# Sheet1.net
KiCad netlist of a schematic drawn in Altium Designer
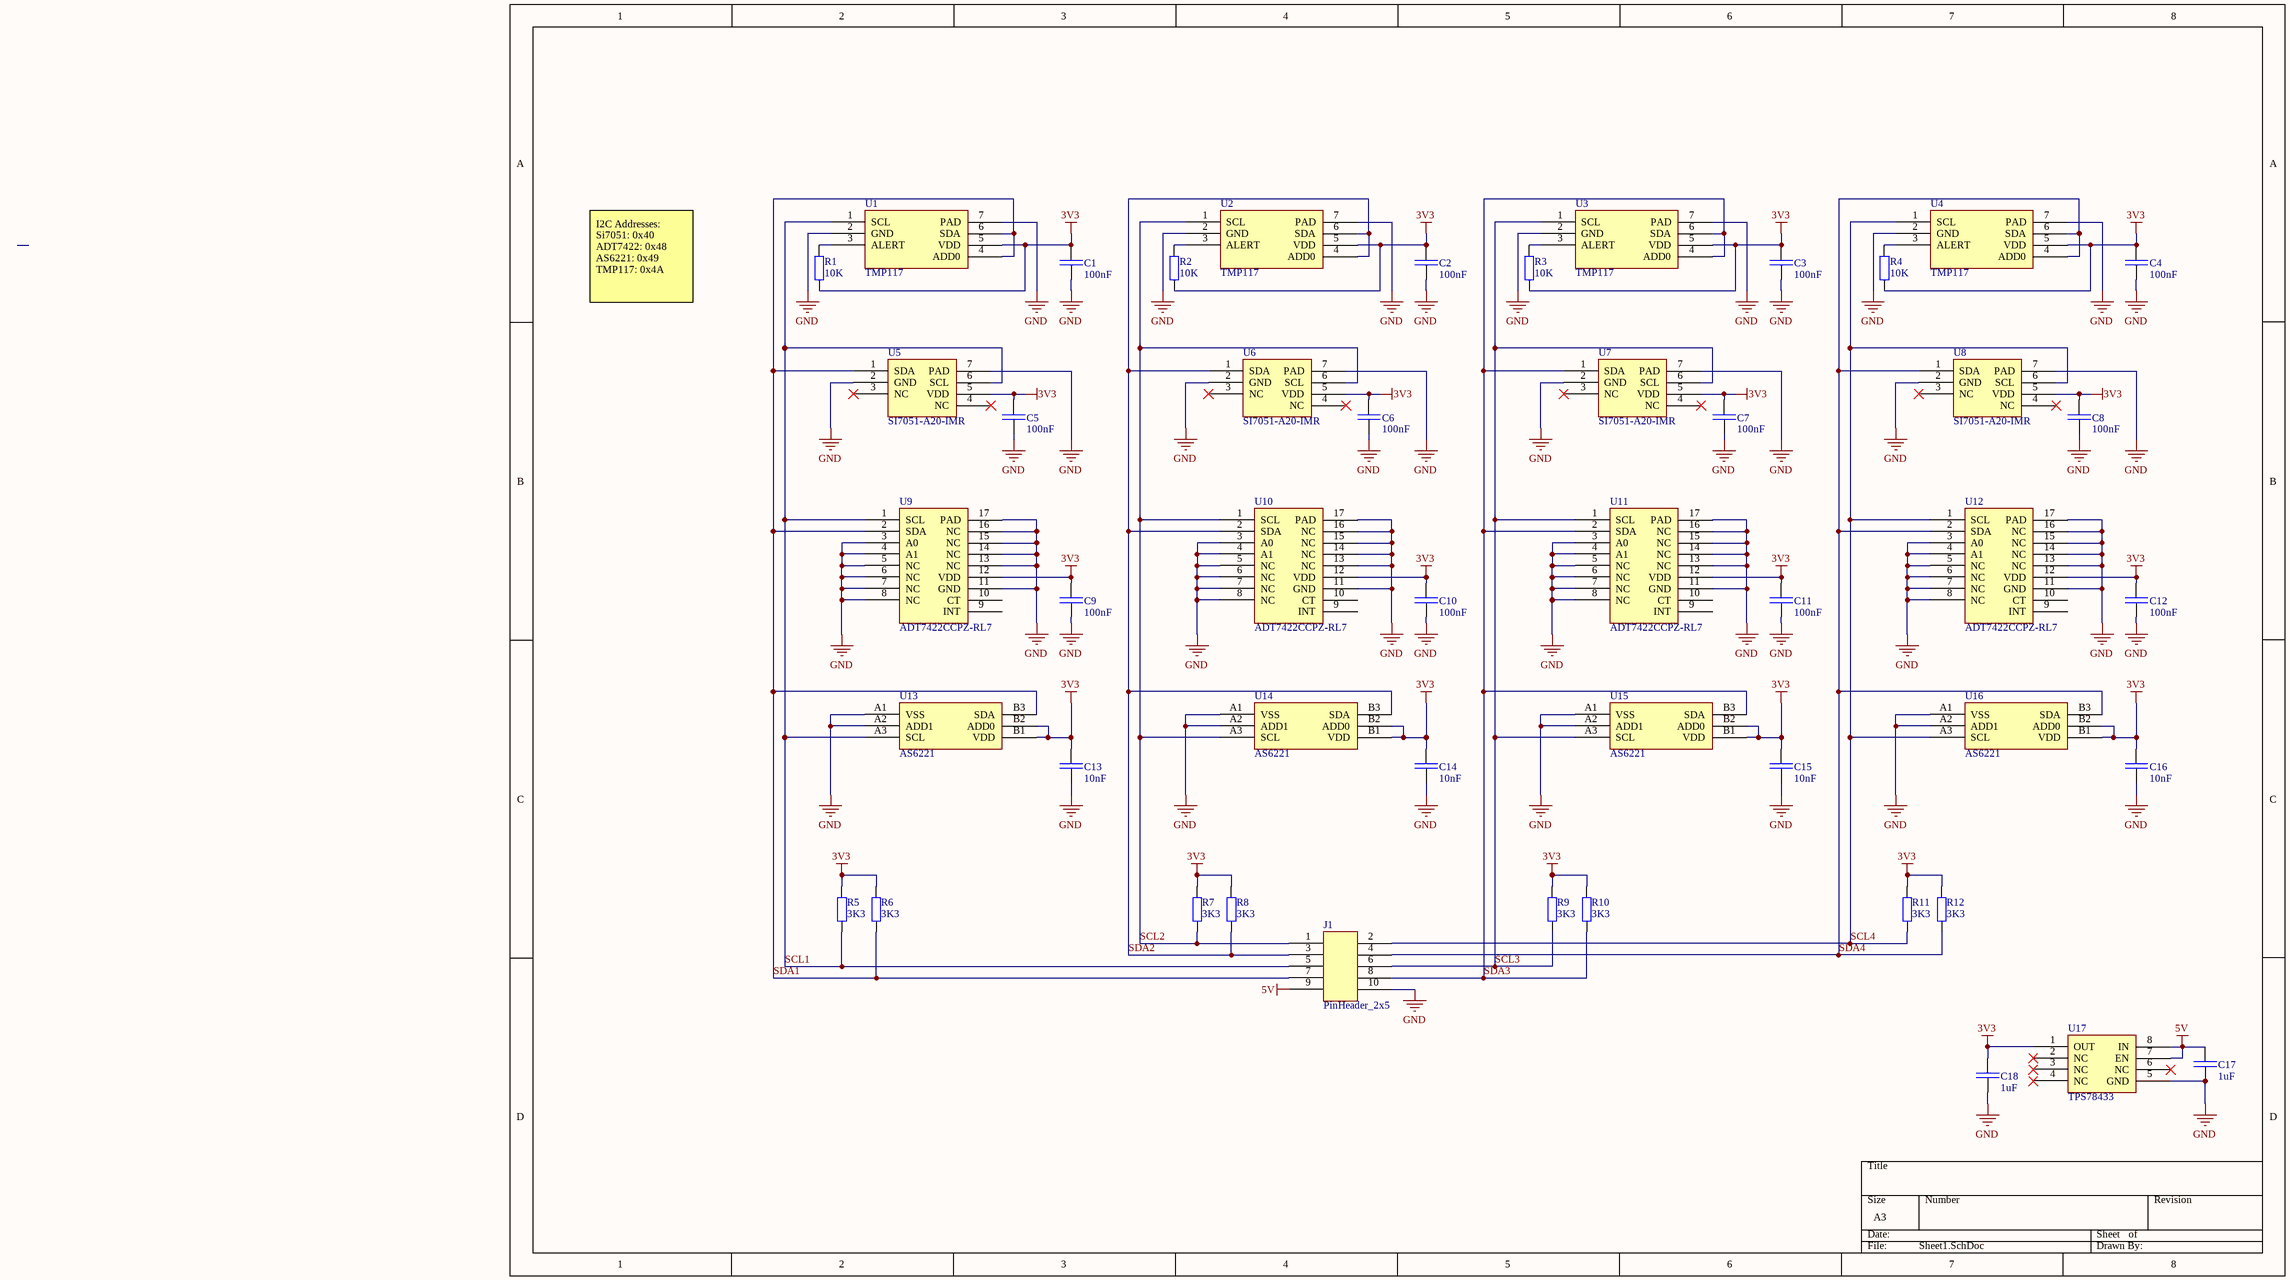
[diagram p0: Sheet1.SchDoc]

(export (version "E")
  (design (tool "Eeschema 10.0.6"))
  (components
    (comp (ref "C1")
      (value "100nF")
      (footprint "CAP_SM0603_YAGEOCC2_N")
      (description "CAP 100nF SM0603 X7R 50V YAGEO CC2")
      (fields
        (field (name "MANUFACTURER") "Yageo")
        (field (name "MANUFACTURER PART NUMBER") "CC0603KRX7R9BB104")
      )
      (libsource (lib "Schlib1") (part "CC0603KRX7R9BB104"))
    )
    (comp (ref "C2")
      (value "100nF")
      (footprint "CAP_SM0603_YAGEOCC2_N")
      (description "CAP 100nF SM0603 X7R 50V YAGEO CC2")
      (fields
        (field (name "MANUFACTURER") "Yageo")
        (field (name "MANUFACTURER PART NUMBER") "CC0603KRX7R9BB104")
      )
      (libsource (lib "Schlib1") (part "CC0603KRX7R9BB104"))
    )
    (comp (ref "C3")
      (value "100nF")
      (footprint "CAP_SM0603_YAGEOCC2_N")
      (description "CAP 100nF SM0603 X7R 50V YAGEO CC2")
      (fields
        (field (name "MANUFACTURER") "Yageo")
        (field (name "MANUFACTURER PART NUMBER") "CC0603KRX7R9BB104")
      )
      (libsource (lib "Schlib1") (part "CC0603KRX7R9BB104"))
    )
    (comp (ref "C4")
      (value "100nF")
      (footprint "CAP_SM0603_YAGEOCC2_N")
      (description "CAP 100nF SM0603 X7R 50V YAGEO CC2")
      (fields
        (field (name "MANUFACTURER") "Yageo")
        (field (name "MANUFACTURER PART NUMBER") "CC0603KRX7R9BB104")
      )
      (libsource (lib "Schlib1") (part "CC0603KRX7R9BB104"))
    )
    (comp (ref "C5")
      (value "100nF")
      (footprint "CAP_SM0603_YAGEOCC2_N")
      (description "CAP 100nF SM0603 X7R 50V YAGEO CC2")
      (fields
        (field (name "MANUFACTURER") "Yageo")
        (field (name "MANUFACTURER PART NUMBER") "CC0603KRX7R9BB104")
      )
      (libsource (lib "Schlib1") (part "CC0603KRX7R9BB104"))
    )
    (comp (ref "C6")
      (value "100nF")
      (footprint "CAP_SM0603_YAGEOCC2_N")
      (description "CAP 100nF SM0603 X7R 50V YAGEO CC2")
      (fields
        (field (name "MANUFACTURER") "Yageo")
        (field (name "MANUFACTURER PART NUMBER") "CC0603KRX7R9BB104")
      )
      (libsource (lib "Schlib1") (part "CC0603KRX7R9BB104"))
    )
    (comp (ref "C7")
      (value "100nF")
      (footprint "CAP_SM0603_YAGEOCC2_N")
      (description "CAP 100nF SM0603 X7R 50V YAGEO CC2")
      (fields
        (field (name "MANUFACTURER") "Yageo")
        (field (name "MANUFACTURER PART NUMBER") "CC0603KRX7R9BB104")
      )
      (libsource (lib "Schlib1") (part "CC0603KRX7R9BB104"))
    )
    (comp (ref "C8")
      (value "100nF")
      (footprint "CAP_SM0603_YAGEOCC2_N")
      (description "CAP 100nF SM0603 X7R 50V YAGEO CC2")
      (fields
        (field (name "MANUFACTURER") "Yageo")
        (field (name "MANUFACTURER PART NUMBER") "CC0603KRX7R9BB104")
      )
      (libsource (lib "Schlib1") (part "CC0603KRX7R9BB104"))
    )
    (comp (ref "C9")
      (value "100nF")
      (footprint "CAP_SM0603_YAGEOCC2_N")
      (description "CAP 100nF SM0603 X7R 50V YAGEO CC2")
      (fields
        (field (name "MANUFACTURER") "Yageo")
        (field (name "MANUFACTURER PART NUMBER") "CC0603KRX7R9BB104")
      )
      (libsource (lib "Schlib1") (part "CC0603KRX7R9BB104"))
    )
    (comp (ref "C10")
      (value "100nF")
      (footprint "CAP_SM0603_YAGEOCC2_N")
      (description "CAP 100nF SM0603 X7R 50V YAGEO CC2")
      (fields
        (field (name "MANUFACTURER") "Yageo")
        (field (name "MANUFACTURER PART NUMBER") "CC0603KRX7R9BB104")
      )
      (libsource (lib "Schlib1") (part "CC0603KRX7R9BB104"))
    )
    (comp (ref "C11")
      (value "100nF")
      (footprint "CAP_SM0603_YAGEOCC2_N")
      (description "CAP 100nF SM0603 X7R 50V YAGEO CC2")
      (fields
        (field (name "MANUFACTURER") "Yageo")
        (field (name "MANUFACTURER PART NUMBER") "CC0603KRX7R9BB104")
      )
      (libsource (lib "Schlib1") (part "CC0603KRX7R9BB104"))
    )
    (comp (ref "C12")
      (value "100nF")
      (footprint "CAP_SM0603_YAGEOCC2_N")
      (description "CAP 100nF SM0603 X7R 50V YAGEO CC2")
      (fields
        (field (name "MANUFACTURER") "Yageo")
        (field (name "MANUFACTURER PART NUMBER") "CC0603KRX7R9BB104")
      )
      (libsource (lib "Schlib1") (part "CC0603KRX7R9BB104"))
    )
    (comp (ref "C13")
      (value "10nF")
      (footprint "CAP_SM0402_YAGEOCC2_N")
      (description "CAP 10nF SM0402 X7R 50V YAGEO CC2")
      (fields
        (field (name "MANUFACTURER") "Yageo")
        (field (name "MANUFACTURER PART NUMBER") "CC0603KRX7R9BB103")
      )
      (libsource (lib "Schlib1") (part "CC0402KRX7R9BB103"))
    )
    (comp (ref "C14")
      (value "10nF")
      (footprint "CAP_SM0402_YAGEOCC2_N")
      (description "CAP 10nF SM0402 X7R 50V YAGEO CC2")
      (fields
        (field (name "MANUFACTURER") "Yageo")
        (field (name "MANUFACTURER PART NUMBER") "CC0603KRX7R9BB103")
      )
      (libsource (lib "Schlib1") (part "CC0402KRX7R9BB103"))
    )
    (comp (ref "C15")
      (value "10nF")
      (footprint "CAP_SM0402_YAGEOCC2_N")
      (description "CAP 10nF SM0402 X7R 50V YAGEO CC2")
      (fields
        (field (name "MANUFACTURER") "Yageo")
        (field (name "MANUFACTURER PART NUMBER") "CC0603KRX7R9BB103")
      )
      (libsource (lib "Schlib1") (part "CC0402KRX7R9BB103"))
    )
    (comp (ref "C16")
      (value "10nF")
      (footprint "CAP_SM0402_YAGEOCC2_N")
      (description "CAP 10nF SM0402 X7R 50V YAGEO CC2")
      (fields
        (field (name "MANUFACTURER") "Yageo")
        (field (name "MANUFACTURER PART NUMBER") "CC0603KRX7R9BB103")
      )
      (libsource (lib "Schlib1") (part "CC0402KRX7R9BB103"))
    )
    (comp (ref "C17")
      (value "1uF")
      (footprint "CAP_SM0805_YAGEOCC2_N")
      (description "CAP 1uF SM0805 X7R 25V YAGEO CC2")
      (fields
        (field (name "MANUFACTURER") "Yageo")
        (field (name "MANUFACTURER PART NUMBER") "CC0805KKX7R8BB105")
      )
      (libsource (lib "symbols") (part "CC0805KKX7R8BB105"))
    )
    (comp (ref "C18")
      (value "1uF")
      (footprint "CAP_SM0805_YAGEOCC2_N")
      (description "CAP 1uF SM0805 X7R 25V YAGEO CC2")
      (fields
        (field (name "MANUFACTURER") "Yageo")
        (field (name "MANUFACTURER PART NUMBER") "CC0805KKX7R8BB105")
      )
      (libsource (lib "symbols") (part "CC0805KKX7R8BB105"))
    )
    (comp (ref "J1")
      (value "PinHeader_2x5")
      (footprint "PinHeader_2x5_2.54mm")
      (description "PinHeader_2x5 2.54mm Pitch")
      (libsource (lib "Schlib1") (part "PinHeader_2x5_2.54mm"))
    )
    (comp (ref "R1")
      (value "10K")
      (footprint "RES_SM0603_YAGEORC_N")
      (description "RES 10K SM0603 YAGEO RC_L")
      (fields
        (field (name "MANUFACTURER") "Yageo")
        (field (name "MANUFACTURER PART NUMBER") "RC0603FR-0710KL")
      )
      (libsource (lib "Schlib1") (part "RC0603FR-0710KL"))
    )
    (comp (ref "R2")
      (value "10K")
      (footprint "RES_SM0603_YAGEORC_N")
      (description "RES 10K SM0603 YAGEO RC_L")
      (fields
        (field (name "MANUFACTURER") "Yageo")
        (field (name "MANUFACTURER PART NUMBER") "RC0603FR-0710KL")
      )
      (libsource (lib "Schlib1") (part "RC0603FR-0710KL"))
    )
    (comp (ref "R3")
      (value "10K")
      (footprint "RES_SM0603_YAGEORC_N")
      (description "RES 10K SM0603 YAGEO RC_L")
      (fields
        (field (name "MANUFACTURER") "Yageo")
        (field (name "MANUFACTURER PART NUMBER") "RC0603FR-0710KL")
      )
      (libsource (lib "Schlib1") (part "RC0603FR-0710KL"))
    )
    (comp (ref "R4")
      (value "10K")
      (footprint "RES_SM0603_YAGEORC_N")
      (description "RES 10K SM0603 YAGEO RC_L")
      (fields
        (field (name "MANUFACTURER") "Yageo")
        (field (name "MANUFACTURER PART NUMBER") "RC0603FR-0710KL")
      )
      (libsource (lib "Schlib1") (part "RC0603FR-0710KL"))
    )
    (comp (ref "R5")
      (value "3K3")
      (footprint "RES_SM0603_YAGEORC_N")
      (description "RES 3.3K SM0603 YAGEO RC_L")
      (fields
        (field (name "MANUFACTURER") "Yageo")
        (field (name "MANUFACTURER PART NUMBER") "RC0603FR-0710KL")
      )
      (libsource (lib "Schlib1") (part "RC0603FR-073K3L"))
    )
    (comp (ref "R6")
      (value "3K3")
      (footprint "RES_SM0603_YAGEORC_N")
      (description "RES 3.3K SM0603 YAGEO RC_L")
      (fields
        (field (name "MANUFACTURER") "Yageo")
        (field (name "MANUFACTURER PART NUMBER") "RC0603FR-0710KL")
      )
      (libsource (lib "Schlib1") (part "RC0603FR-073K3L"))
    )
    (comp (ref "R7")
      (value "3K3")
      (footprint "RES_SM0603_YAGEORC_N")
      (description "RES 3.3K SM0603 YAGEO RC_L")
      (fields
        (field (name "MANUFACTURER") "Yageo")
        (field (name "MANUFACTURER PART NUMBER") "RC0603FR-0710KL")
      )
      (libsource (lib "Schlib1") (part "RC0603FR-073K3L"))
    )
    (comp (ref "R8")
      (value "3K3")
      (footprint "RES_SM0603_YAGEORC_N")
      (description "RES 3.3K SM0603 YAGEO RC_L")
      (fields
        (field (name "MANUFACTURER") "Yageo")
        (field (name "MANUFACTURER PART NUMBER") "RC0603FR-0710KL")
      )
      (libsource (lib "Schlib1") (part "RC0603FR-073K3L"))
    )
    (comp (ref "R9")
      (value "3K3")
      (footprint "RES_SM0603_YAGEORC_N")
      (description "RES 3.3K SM0603 YAGEO RC_L")
      (fields
        (field (name "MANUFACTURER") "Yageo")
        (field (name "MANUFACTURER PART NUMBER") "RC0603FR-0710KL")
      )
      (libsource (lib "Schlib1") (part "RC0603FR-073K3L"))
    )
    (comp (ref "R10")
      (value "3K3")
      (footprint "RES_SM0603_YAGEORC_N")
      (description "RES 3.3K SM0603 YAGEO RC_L")
      (fields
        (field (name "MANUFACTURER") "Yageo")
        (field (name "MANUFACTURER PART NUMBER") "RC0603FR-0710KL")
      )
      (libsource (lib "Schlib1") (part "RC0603FR-073K3L"))
    )
    (comp (ref "R11")
      (value "3K3")
      (footprint "RES_SM0603_YAGEORC_N")
      (description "RES 3.3K SM0603 YAGEO RC_L")
      (fields
        (field (name "MANUFACTURER") "Yageo")
        (field (name "MANUFACTURER PART NUMBER") "RC0603FR-0710KL")
      )
      (libsource (lib "Schlib1") (part "RC0603FR-073K3L"))
    )
    (comp (ref "R12")
      (value "3K3")
      (footprint "RES_SM0603_YAGEORC_N")
      (description "RES 3.3K SM0603 YAGEO RC_L")
      (fields
        (field (name "MANUFACTURER") "Yageo")
        (field (name "MANUFACTURER PART NUMBER") "RC0603FR-0710KL")
      )
      (libsource (lib "Schlib1") (part "RC0603FR-073K3L"))
    )
    (comp (ref "U1")
      (value "TMP117")
      (footprint "TMP117(N/M)AIDRV_WSON")
      (description "TMP117 High-Accuracy, Low-Power, Digital Temperature Sensor, -55°C bis 150°C, 16b 6-WSON (2x2)")
      (libsource (lib "Schlib1") (part "TMP117NAIDRVR"))
    )
    (comp (ref "U2")
      (value "TMP117")
      (footprint "TMP117(N/M)AIDRV_WSON")
      (description "TMP117 High-Accuracy, Low-Power, Digital Temperature Sensor, -55°C bis 150°C, 16b 6-WSON (2x2)")
      (libsource (lib "Schlib1") (part "TMP117NAIDRVR"))
    )
    (comp (ref "U3")
      (value "TMP117")
      (footprint "TMP117(N/M)AIDRV_WSON")
      (description "TMP117 High-Accuracy, Low-Power, Digital Temperature Sensor, -55°C bis 150°C, 16b 6-WSON (2x2)")
      (libsource (lib "Schlib1") (part "TMP117NAIDRVR"))
    )
    (comp (ref "U4")
      (value "TMP117")
      (footprint "TMP117(N/M)AIDRV_WSON")
      (description "TMP117 High-Accuracy, Low-Power, Digital Temperature Sensor, -55°C bis 150°C, 16b 6-WSON (2x2)")
      (libsource (lib "Schlib1") (part "TMP117NAIDRVR"))
    )
    (comp (ref "U5")
      (value "SI7051-A20-IMR")
      (footprint "SI7050/1/2/3/4/5")
      (description "Si7051-A20 Temperature Sensor ±0.1°C maximum accuracy, Digital I2C, -40°C ~ 125°C 14b 6-DFN (3x3)")
      (libsource (lib "Schlib1") (part "SI7051-A20-IMR"))
    )
    (comp (ref "U6")
      (value "SI7051-A20-IMR")
      (footprint "SI7050/1/2/3/4/5")
      (description "Si7051-A20 Temperature Sensor ±0.1°C maximum accuracy, Digital I2C, -40°C ~ 125°C 14b 6-DFN (3x3)")
      (libsource (lib "Schlib1") (part "SI7051-A20-IMR"))
    )
    (comp (ref "U7")
      (value "SI7051-A20-IMR")
      (footprint "SI7050/1/2/3/4/5")
      (description "Si7051-A20 Temperature Sensor ±0.1°C maximum accuracy, Digital I2C, -40°C ~ 125°C 14b 6-DFN (3x3)")
      (libsource (lib "Schlib1") (part "SI7051-A20-IMR"))
    )
    (comp (ref "U8")
      (value "SI7051-A20-IMR")
      (footprint "SI7050/1/2/3/4/5")
      (description "Si7051-A20 Temperature Sensor ±0.1°C maximum accuracy, Digital I2C, -40°C ~ 125°C 14b 6-DFN (3x3)")
      (libsource (lib "Schlib1") (part "SI7051-A20-IMR"))
    )
    (comp (ref "U9")
      (value "ADT7422CCPZ-RL7")
      (footprint "ADT7422_QFN")
      (libsource (lib "Schlib1") (part "ADT7422CCPZ-RL7"))
    )
    (comp (ref "U10")
      (value "ADT7422CCPZ-RL7")
      (footprint "ADT7422_QFN")
      (libsource (lib "Schlib1") (part "ADT7422CCPZ-RL7"))
    )
    (comp (ref "U11")
      (value "ADT7422CCPZ-RL7")
      (footprint "ADT7422_QFN")
      (libsource (lib "Schlib1") (part "ADT7422CCPZ-RL7"))
    )
    (comp (ref "U12")
      (value "ADT7422CCPZ-RL7")
      (footprint "ADT7422_QFN")
      (libsource (lib "Schlib1") (part "ADT7422CCPZ-RL7"))
    )
    (comp (ref "U13")
      (value "AS6221")
      (footprint "AS6221_BGA")
      (description "AS6221 Temperature Sensor Digital -40°C ~ 125°C 16b 6-WLCSP (1.5x1.03)")
      (libsource (lib "Schlib1") (part "AS6221-AWLT-S"))
    )
    (comp (ref "U14")
      (value "AS6221")
      (footprint "AS6221_BGA")
      (description "AS6221 Temperature Sensor Digital -40°C ~ 125°C 16b 6-WLCSP (1.5x1.03)")
      (libsource (lib "Schlib1") (part "AS6221-AWLT-S"))
    )
    (comp (ref "U15")
      (value "AS6221")
      (footprint "AS6221_BGA")
      (description "AS6221 Temperature Sensor Digital -40°C ~ 125°C 16b 6-WLCSP (1.5x1.03)")
      (libsource (lib "Schlib1") (part "AS6221-AWLT-S"))
    )
    (comp (ref "U16")
      (value "AS6221")
      (footprint "AS6221_BGA")
      (description "AS6221 Temperature Sensor Digital -40°C ~ 125°C 16b 6-WLCSP (1.5x1.03)")
      (libsource (lib "Schlib1") (part "AS6221-AWLT-S"))
    )
    (comp (ref "U17")
      (value "TPS78433")
      (footprint "TPS784xxxQDRBRQ1_SON")
      (libsource (lib "symbols") (part "TPS78433QWDRBRQ1"))
    )
  )
  (nets
    (net (code "1") (name "/SCL1") (class "Default")
      (node (ref "J1") (pin "5") (pintype "passive"))
      (node (ref "R5") (pin "1") (pintype "passive"))
      (node (ref "U1") (pin "1") (pinfunction "SCL_1") (pintype "passive"))
      (node (ref "U13") (pin "A3") (pinfunction "SCL_A3") (pintype "passive"))
      (node (ref "U5") (pin "6") (pinfunction "SCL_6") (pintype "passive"))
      (node (ref "U9") (pin "1") (pinfunction "SCL_1") (pintype "passive"))
    )
    (net (code "2") (name "/SCL2") (class "Default")
      (node (ref "J1") (pin "1") (pintype "passive"))
      (node (ref "R7") (pin "1") (pintype "passive"))
      (node (ref "U10") (pin "1") (pinfunction "SCL_1") (pintype "passive"))
      (node (ref "U14") (pin "A3") (pinfunction "SCL_A3") (pintype "passive"))
      (node (ref "U2") (pin "1") (pinfunction "SCL_1") (pintype "passive"))
      (node (ref "U6") (pin "6") (pinfunction "SCL_6") (pintype "passive"))
    )
    (net (code "3") (name "/SCL3") (class "Default")
      (node (ref "J1") (pin "6") (pintype "passive"))
      (node (ref "R9") (pin "1") (pintype "passive"))
      (node (ref "U11") (pin "1") (pinfunction "SCL_1") (pintype "passive"))
      (node (ref "U15") (pin "A3") (pinfunction "SCL_A3") (pintype "passive"))
      (node (ref "U3") (pin "1") (pinfunction "SCL_1") (pintype "passive"))
      (node (ref "U7") (pin "6") (pinfunction "SCL_6") (pintype "passive"))
    )
    (net (code "4") (name "/SCL4") (class "Default")
      (node (ref "J1") (pin "2") (pintype "passive"))
      (node (ref "R11") (pin "1") (pintype "passive"))
      (node (ref "U12") (pin "1") (pinfunction "SCL_1") (pintype "passive"))
      (node (ref "U16") (pin "A3") (pinfunction "SCL_A3") (pintype "passive"))
      (node (ref "U4") (pin "1") (pinfunction "SCL_1") (pintype "passive"))
      (node (ref "U8") (pin "6") (pinfunction "SCL_6") (pintype "passive"))
    )
    (net (code "5") (name "/SDA1") (class "Default")
      (node (ref "J1") (pin "7") (pintype "passive"))
      (node (ref "R6") (pin "1") (pintype "passive"))
      (node (ref "U1") (pin "4") (pinfunction "ADD0_4") (pintype "passive"))
      (node (ref "U1") (pin "6") (pinfunction "SDA_6") (pintype "passive"))
      (node (ref "U13") (pin "B3") (pinfunction "SDA_B3") (pintype "passive"))
      (node (ref "U5") (pin "1") (pinfunction "SDA_1") (pintype "passive"))
      (node (ref "U9") (pin "2") (pinfunction "SDA_2") (pintype "passive"))
    )
    (net (code "6") (name "/SDA2") (class "Default")
      (node (ref "J1") (pin "3") (pintype "passive"))
      (node (ref "R8") (pin "1") (pintype "passive"))
      (node (ref "U10") (pin "2") (pinfunction "SDA_2") (pintype "passive"))
      (node (ref "U14") (pin "B3") (pinfunction "SDA_B3") (pintype "passive"))
      (node (ref "U2") (pin "4") (pinfunction "ADD0_4") (pintype "passive"))
      (node (ref "U2") (pin "6") (pinfunction "SDA_6") (pintype "passive"))
      (node (ref "U6") (pin "1") (pinfunction "SDA_1") (pintype "passive"))
    )
    (net (code "7") (name "/SDA3") (class "Default")
      (node (ref "J1") (pin "8") (pintype "passive"))
      (node (ref "R10") (pin "1") (pintype "passive"))
      (node (ref "U11") (pin "2") (pinfunction "SDA_2") (pintype "passive"))
      (node (ref "U15") (pin "B3") (pinfunction "SDA_B3") (pintype "passive"))
      (node (ref "U3") (pin "4") (pinfunction "ADD0_4") (pintype "passive"))
      (node (ref "U3") (pin "6") (pinfunction "SDA_6") (pintype "passive"))
      (node (ref "U7") (pin "1") (pinfunction "SDA_1") (pintype "passive"))
    )
    (net (code "8") (name "/SDA4") (class "Default")
      (node (ref "J1") (pin "4") (pintype "passive"))
      (node (ref "R12") (pin "1") (pintype "passive"))
      (node (ref "U12") (pin "2") (pinfunction "SDA_2") (pintype "passive"))
      (node (ref "U16") (pin "B3") (pinfunction "SDA_B3") (pintype "passive"))
      (node (ref "U4") (pin "4") (pinfunction "ADD0_4") (pintype "passive"))
      (node (ref "U4") (pin "6") (pinfunction "SDA_6") (pintype "passive"))
      (node (ref "U8") (pin "1") (pinfunction "SDA_1") (pintype "passive"))
    )
    (net (code "9") (name "3V3") (class "Default")
      (node (ref "C1") (pin "2") (pintype "passive"))
      (node (ref "C10") (pin "2") (pintype "passive"))
      (node (ref "C11") (pin "2") (pintype "passive"))
      (node (ref "C12") (pin "2") (pintype "passive"))
      (node (ref "C13") (pin "1") (pintype "passive"))
      (node (ref "C14") (pin "1") (pintype "passive"))
      (node (ref "C15") (pin "1") (pintype "passive"))
      (node (ref "C16") (pin "1") (pintype "passive"))
      (node (ref "C18") (pin "2") (pintype "passive"))
      (node (ref "C2") (pin "2") (pintype "passive"))
      (node (ref "C3") (pin "2") (pintype "passive"))
      (node (ref "C4") (pin "2") (pintype "passive"))
      (node (ref "C5") (pin "2") (pintype "passive"))
      (node (ref "C6") (pin "2") (pintype "passive"))
      (node (ref "C7") (pin "2") (pintype "passive"))
      (node (ref "C8") (pin "2") (pintype "passive"))
      (node (ref "C9") (pin "2") (pintype "passive"))
      (node (ref "R1") (pin "1") (pintype "passive"))
      (node (ref "R10") (pin "2") (pintype "passive"))
      (node (ref "R11") (pin "2") (pintype "passive"))
      (node (ref "R12") (pin "2") (pintype "passive"))
      (node (ref "R2") (pin "1") (pintype "passive"))
      (node (ref "R3") (pin "1") (pintype "passive"))
      (node (ref "R4") (pin "1") (pintype "passive"))
      (node (ref "R5") (pin "2") (pintype "passive"))
      (node (ref "R6") (pin "2") (pintype "passive"))
      (node (ref "R7") (pin "2") (pintype "passive"))
      (node (ref "R8") (pin "2") (pintype "passive"))
      (node (ref "R9") (pin "2") (pintype "passive"))
      (node (ref "U1") (pin "5") (pinfunction "VDD_5") (pintype "passive"))
      (node (ref "U10") (pin "12") (pinfunction "VDD_12") (pintype "passive"))
      (node (ref "U11") (pin "12") (pinfunction "VDD_12") (pintype "passive"))
      (node (ref "U12") (pin "12") (pinfunction "VDD_12") (pintype "passive"))
      (node (ref "U13") (pin "B1") (pinfunction "VDD_B1") (pintype "passive"))
      (node (ref "U13") (pin "B2") (pinfunction "ADD0_B2") (pintype "passive"))
      (node (ref "U14") (pin "B1") (pinfunction "VDD_B1") (pintype "passive"))
      (node (ref "U14") (pin "B2") (pinfunction "ADD0_B2") (pintype "passive"))
      (node (ref "U15") (pin "B1") (pinfunction "VDD_B1") (pintype "passive"))
      (node (ref "U15") (pin "B2") (pinfunction "ADD0_B2") (pintype "passive"))
      (node (ref "U16") (pin "B1") (pinfunction "VDD_B1") (pintype "passive"))
      (node (ref "U16") (pin "B2") (pinfunction "ADD0_B2") (pintype "passive"))
      (node (ref "U17") (pin "1") (pinfunction "OUT_1") (pintype "passive"))
      (node (ref "U2") (pin "5") (pinfunction "VDD_5") (pintype "passive"))
      (node (ref "U3") (pin "5") (pinfunction "VDD_5") (pintype "passive"))
      (node (ref "U4") (pin "5") (pinfunction "VDD_5") (pintype "passive"))
      (node (ref "U5") (pin "5") (pinfunction "VDD_5") (pintype "passive"))
      (node (ref "U6") (pin "5") (pinfunction "VDD_5") (pintype "passive"))
      (node (ref "U7") (pin "5") (pinfunction "VDD_5") (pintype "passive"))
      (node (ref "U8") (pin "5") (pinfunction "VDD_5") (pintype "passive"))
      (node (ref "U9") (pin "12") (pinfunction "VDD_12") (pintype "passive"))
    )
    (net (code "10") (name "5V") (class "Default")
      (node (ref "C17") (pin "2") (pintype "passive"))
      (node (ref "J1") (pin "9") (pintype "passive"))
      (node (ref "U17") (pin "7") (pinfunction "EN_7") (pintype "passive"))
      (node (ref "U17") (pin "8") (pinfunction "IN_8") (pintype "passive"))
    )
    (net (code "11") (name "GND") (class "Default")
      (node (ref "C1") (pin "1") (pintype "passive"))
      (node (ref "C10") (pin "1") (pintype "passive"))
      (node (ref "C11") (pin "1") (pintype "passive"))
      (node (ref "C12") (pin "1") (pintype "passive"))
      (node (ref "C13") (pin "2") (pintype "passive"))
      (node (ref "C14") (pin "2") (pintype "passive"))
      (node (ref "C15") (pin "2") (pintype "passive"))
      (node (ref "C16") (pin "2") (pintype "passive"))
      (node (ref "C17") (pin "1") (pintype "passive"))
      (node (ref "C18") (pin "1") (pintype "passive"))
      (node (ref "C2") (pin "1") (pintype "passive"))
      (node (ref "C3") (pin "1") (pintype "passive"))
      (node (ref "C4") (pin "1") (pintype "passive"))
      (node (ref "C5") (pin "1") (pintype "passive"))
      (node (ref "C6") (pin "1") (pintype "passive"))
      (node (ref "C7") (pin "1") (pintype "passive"))
      (node (ref "C8") (pin "1") (pintype "passive"))
      (node (ref "C9") (pin "1") (pintype "passive"))
      (node (ref "J1") (pin "10") (pintype "passive"))
      (node (ref "U1") (pin "2") (pinfunction "GND_2") (pintype "passive"))
      (node (ref "U1") (pin "7") (pinfunction "PAD_7") (pintype "passive"))
      (node (ref "U10") (pin "11") (pinfunction "GND_11") (pintype "passive"))
      (node (ref "U10") (pin "13") (pinfunction "NC_13") (pintype "passive"))
      (node (ref "U10") (pin "14") (pinfunction "NC_14") (pintype "passive"))
      (node (ref "U10") (pin "15") (pinfunction "NC_15") (pintype "passive"))
      (node (ref "U10") (pin "16") (pinfunction "NC_16") (pintype "passive"))
      (node (ref "U10") (pin "17") (pinfunction "PAD_17") (pintype "passive"))
      (node (ref "U10") (pin "3") (pinfunction "A0_3") (pintype "passive"))
      (node (ref "U10") (pin "4") (pinfunction "A1_4") (pintype "passive"))
      (node (ref "U10") (pin "5") (pinfunction "NC_5") (pintype "passive"))
      (node (ref "U10") (pin "6") (pinfunction "NC_6") (pintype "passive"))
      (node (ref "U10") (pin "7") (pinfunction "NC_7") (pintype "passive"))
      (node (ref "U10") (pin "8") (pinfunction "NC_8") (pintype "passive"))
      (node (ref "U11") (pin "11") (pinfunction "GND_11") (pintype "passive"))
      (node (ref "U11") (pin "13") (pinfunction "NC_13") (pintype "passive"))
      (node (ref "U11") (pin "14") (pinfunction "NC_14") (pintype "passive"))
      (node (ref "U11") (pin "15") (pinfunction "NC_15") (pintype "passive"))
      (node (ref "U11") (pin "16") (pinfunction "NC_16") (pintype "passive"))
      (node (ref "U11") (pin "17") (pinfunction "PAD_17") (pintype "passive"))
      (node (ref "U11") (pin "3") (pinfunction "A0_3") (pintype "passive"))
      (node (ref "U11") (pin "4") (pinfunction "A1_4") (pintype "passive"))
      (node (ref "U11") (pin "5") (pinfunction "NC_5") (pintype "passive"))
      (node (ref "U11") (pin "6") (pinfunction "NC_6") (pintype "passive"))
      (node (ref "U11") (pin "7") (pinfunction "NC_7") (pintype "passive"))
      (node (ref "U11") (pin "8") (pinfunction "NC_8") (pintype "passive"))
      (node (ref "U12") (pin "11") (pinfunction "GND_11") (pintype "passive"))
      (node (ref "U12") (pin "13") (pinfunction "NC_13") (pintype "passive"))
      (node (ref "U12") (pin "14") (pinfunction "NC_14") (pintype "passive"))
      (node (ref "U12") (pin "15") (pinfunction "NC_15") (pintype "passive"))
      (node (ref "U12") (pin "16") (pinfunction "NC_16") (pintype "passive"))
      (node (ref "U12") (pin "17") (pinfunction "PAD_17") (pintype "passive"))
      (node (ref "U12") (pin "3") (pinfunction "A0_3") (pintype "passive"))
      (node (ref "U12") (pin "4") (pinfunction "A1_4") (pintype "passive"))
      (node (ref "U12") (pin "5") (pinfunction "NC_5") (pintype "passive"))
      (node (ref "U12") (pin "6") (pinfunction "NC_6") (pintype "passive"))
      (node (ref "U12") (pin "7") (pinfunction "NC_7") (pintype "passive"))
      (node (ref "U12") (pin "8") (pinfunction "NC_8") (pintype "passive"))
      (node (ref "U13") (pin "A1") (pinfunction "VSS_A1") (pintype "passive"))
      (node (ref "U13") (pin "A2") (pinfunction "ADD1_A2") (pintype "passive"))
      (node (ref "U14") (pin "A1") (pinfunction "VSS_A1") (pintype "passive"))
      (node (ref "U14") (pin "A2") (pinfunction "ADD1_A2") (pintype "passive"))
      (node (ref "U15") (pin "A1") (pinfunction "VSS_A1") (pintype "passive"))
      (node (ref "U15") (pin "A2") (pinfunction "ADD1_A2") (pintype "passive"))
      (node (ref "U16") (pin "A1") (pinfunction "VSS_A1") (pintype "passive"))
      (node (ref "U16") (pin "A2") (pinfunction "ADD1_A2") (pintype "passive"))
      (node (ref "U17") (pin "5") (pinfunction "GND_5") (pintype "passive"))
      (node (ref "U2") (pin "2") (pinfunction "GND_2") (pintype "passive"))
      (node (ref "U2") (pin "7") (pinfunction "PAD_7") (pintype "passive"))
      (node (ref "U3") (pin "2") (pinfunction "GND_2") (pintype "passive"))
      (node (ref "U3") (pin "7") (pinfunction "PAD_7") (pintype "passive"))
      (node (ref "U4") (pin "2") (pinfunction "GND_2") (pintype "passive"))
      (node (ref "U4") (pin "7") (pinfunction "PAD_7") (pintype "passive"))
      (node (ref "U5") (pin "2") (pinfunction "GND_2") (pintype "passive"))
      (node (ref "U5") (pin "7") (pinfunction "PAD_7") (pintype "passive"))
      (node (ref "U6") (pin "2") (pinfunction "GND_2") (pintype "passive"))
      (node (ref "U6") (pin "7") (pinfunction "PAD_7") (pintype "passive"))
      (node (ref "U7") (pin "2") (pinfunction "GND_2") (pintype "passive"))
      (node (ref "U7") (pin "7") (pinfunction "PAD_7") (pintype "passive"))
      (node (ref "U8") (pin "2") (pinfunction "GND_2") (pintype "passive"))
      (node (ref "U8") (pin "7") (pinfunction "PAD_7") (pintype "passive"))
      (node (ref "U9") (pin "11") (pinfunction "GND_11") (pintype "passive"))
      (node (ref "U9") (pin "13") (pinfunction "NC_13") (pintype "passive"))
      (node (ref "U9") (pin "14") (pinfunction "NC_14") (pintype "passive"))
      (node (ref "U9") (pin "15") (pinfunction "NC_15") (pintype "passive"))
      (node (ref "U9") (pin "16") (pinfunction "NC_16") (pintype "passive"))
      (node (ref "U9") (pin "17") (pinfunction "PAD_17") (pintype "passive"))
      (node (ref "U9") (pin "3") (pinfunction "A0_3") (pintype "passive"))
      (node (ref "U9") (pin "4") (pinfunction "A1_4") (pintype "passive"))
      (node (ref "U9") (pin "5") (pinfunction "NC_5") (pintype "passive"))
      (node (ref "U9") (pin "6") (pinfunction "NC_6") (pintype "passive"))
      (node (ref "U9") (pin "7") (pinfunction "NC_7") (pintype "passive"))
      (node (ref "U9") (pin "8") (pinfunction "NC_8") (pintype "passive"))
    )
    (net (code "12") (name "Net-(U1-ALERT)") (class "Default")
      (node (ref "R1") (pin "2") (pintype "passive"))
      (node (ref "U1") (pin "3") (pinfunction "ALERT_3") (pintype "passive"))
    )
    (net (code "13") (name "Net-(U2-ALERT)") (class "Default")
      (node (ref "R2") (pin "2") (pintype "passive"))
      (node (ref "U2") (pin "3") (pinfunction "ALERT_3") (pintype "passive"))
    )
    (net (code "14") (name "Net-(U3-ALERT)") (class "Default")
      (node (ref "R3") (pin "2") (pintype "passive"))
      (node (ref "U3") (pin "3") (pinfunction "ALERT_3") (pintype "passive"))
    )
    (net (code "15") (name "Net-(U4-ALERT)") (class "Default")
      (node (ref "R4") (pin "2") (pintype "passive"))
      (node (ref "U4") (pin "3") (pinfunction "ALERT_3") (pintype "passive"))
    )
    (net (code "16") (name "unconnected-(U5-NC-Pad3)") (class "Default")
      (node (ref "U5") (pin "3") (pinfunction "NC_3") (pintype "passive+no_connect"))
    )
    (net (code "17") (name "unconnected-(U5-NC-Pad4)") (class "Default")
      (node (ref "U5") (pin "4") (pinfunction "NC_4") (pintype "passive+no_connect"))
    )
    (net (code "18") (name "unconnected-(U6-NC-Pad3)") (class "Default")
      (node (ref "U6") (pin "3") (pinfunction "NC_3") (pintype "passive+no_connect"))
    )
    (net (code "19") (name "unconnected-(U6-NC-Pad4)") (class "Default")
      (node (ref "U6") (pin "4") (pinfunction "NC_4") (pintype "passive+no_connect"))
    )
    (net (code "20") (name "unconnected-(U7-NC-Pad3)") (class "Default")
      (node (ref "U7") (pin "3") (pinfunction "NC_3") (pintype "passive+no_connect"))
    )
    (net (code "21") (name "unconnected-(U7-NC-Pad4)") (class "Default")
      (node (ref "U7") (pin "4") (pinfunction "NC_4") (pintype "passive+no_connect"))
    )
    (net (code "22") (name "unconnected-(U8-NC-Pad3)") (class "Default")
      (node (ref "U8") (pin "3") (pinfunction "NC_3") (pintype "passive+no_connect"))
    )
    (net (code "23") (name "unconnected-(U8-NC-Pad4)") (class "Default")
      (node (ref "U8") (pin "4") (pinfunction "NC_4") (pintype "passive+no_connect"))
    )
    (net (code "24") (name "unconnected-(U9-CT-Pad10)") (class "Default")
      (node (ref "U9") (pin "10") (pinfunction "CT_10") (pintype "passive"))
    )
    (net (code "25") (name "unconnected-(U9-INT-Pad9)") (class "Default")
      (node (ref "U9") (pin "9") (pinfunction "INT_9") (pintype "passive"))
    )
    (net (code "26") (name "unconnected-(U10-CT-Pad10)") (class "Default")
      (node (ref "U10") (pin "10") (pinfunction "CT_10") (pintype "passive"))
    )
    (net (code "27") (name "unconnected-(U10-INT-Pad9)") (class "Default")
      (node (ref "U10") (pin "9") (pinfunction "INT_9") (pintype "passive"))
    )
    (net (code "28") (name "unconnected-(U11-CT-Pad10)") (class "Default")
      (node (ref "U11") (pin "10") (pinfunction "CT_10") (pintype "passive"))
    )
    (net (code "29") (name "unconnected-(U11-INT-Pad9)") (class "Default")
      (node (ref "U11") (pin "9") (pinfunction "INT_9") (pintype "passive"))
    )
    (net (code "30") (name "unconnected-(U12-CT-Pad10)") (class "Default")
      (node (ref "U12") (pin "10") (pinfunction "CT_10") (pintype "passive"))
    )
    (net (code "31") (name "unconnected-(U12-INT-Pad9)") (class "Default")
      (node (ref "U12") (pin "9") (pinfunction "INT_9") (pintype "passive"))
    )
    (net (code "32") (name "unconnected-(U17-NC-Pad2)") (class "Default")
      (node (ref "U17") (pin "2") (pinfunction "NC_2") (pintype "passive+no_connect"))
    )
    (net (code "33") (name "unconnected-(U17-NC-Pad3)") (class "Default")
      (node (ref "U17") (pin "3") (pinfunction "NC_3") (pintype "passive+no_connect"))
    )
    (net (code "34") (name "unconnected-(U17-NC-Pad4)") (class "Default")
      (node (ref "U17") (pin "4") (pinfunction "NC_4") (pintype "passive+no_connect"))
    )
    (net (code "35") (name "unconnected-(U17-NC-Pad6)") (class "Default")
      (node (ref "U17") (pin "6") (pinfunction "NC_6") (pintype "passive+no_connect"))
    )
  )
)
